# Sheet1.net
KiCad netlist of a schematic drawn in Altium Designer
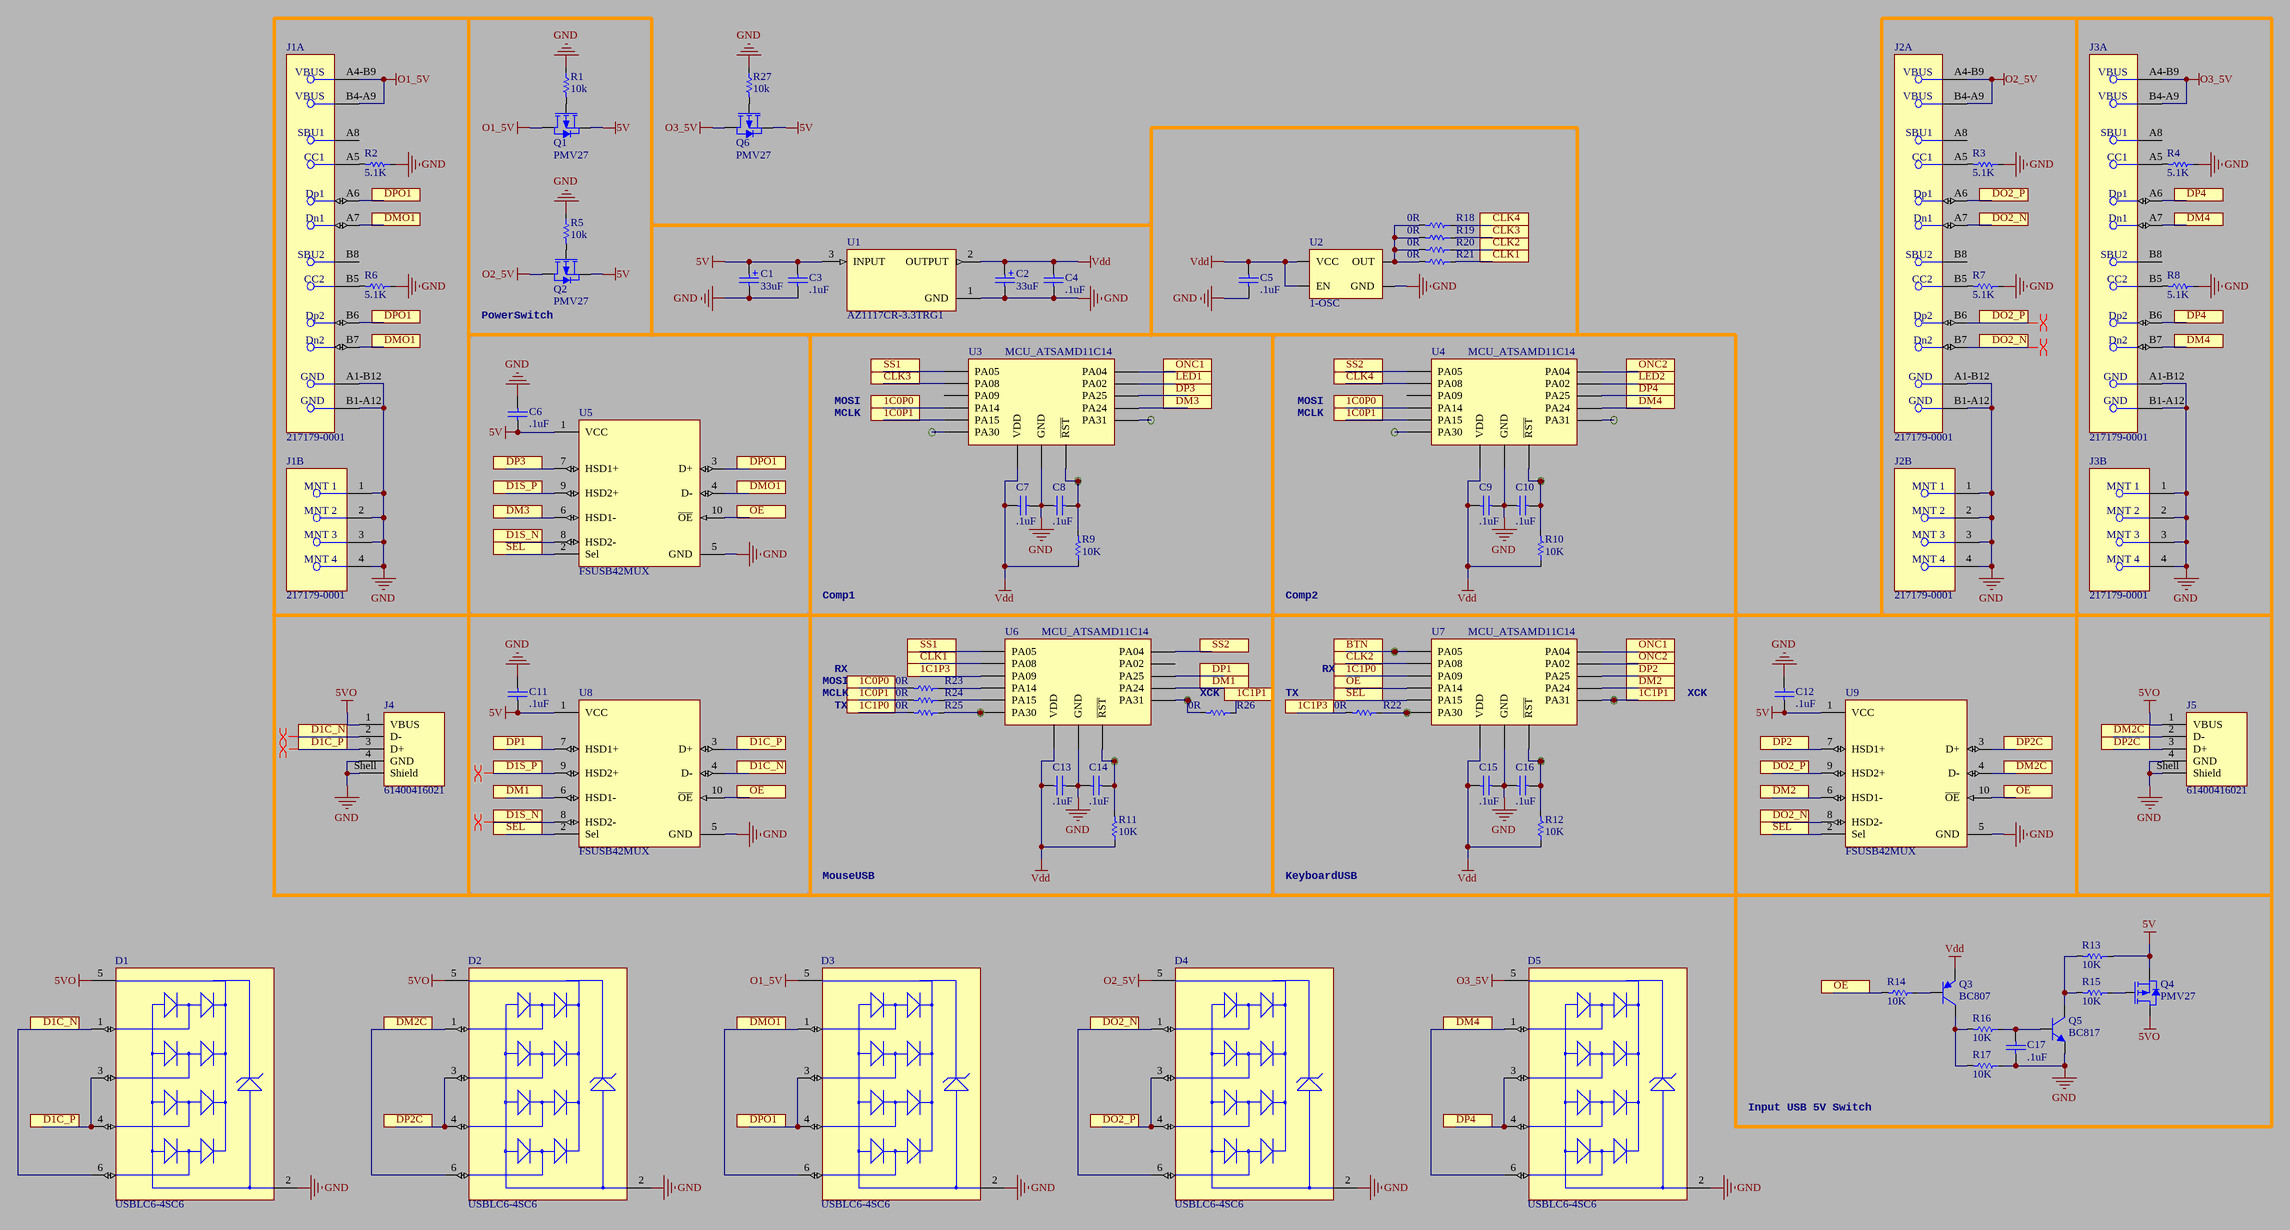
[diagram p0: Sheet1.SchDoc]

(export (version "E")
  (design (tool "Eeschema 10.0.6"))
  (components
    (comp (ref "C1")
      (value "33uF")
      (footprint "TH CAP AL-6.3X11MM-A1K2")
      (description "CAP, CER")
      (fields (field (name "Comment") "Cap Non-Pol"))
      (libsource (lib "A_Passive") (part "-Cap Pol"))
    )
    (comp (ref "C2")
      (value "33uF")
      (footprint "TH CAP AL-6.3X11MM-A1K2")
      (description "CAP, CER")
      (fields (field (name "Comment") "Cap Non-Pol"))
      (libsource (lib "A_Passive") (part "-Cap Pol"))
    )
    (comp (ref "C3")
      (value ".1uF")
      (footprint "Size_0603_N")
      (description "=Value")
      (fields (field (name "Comment") ".1uF, *, *, *, Size_0603_N"))
      (libsource (lib "A_Passive") (part "-Cap Non-Pol"))
    )
    (comp (ref "C4")
      (value ".1uF")
      (footprint "Size_0603_N")
      (description "=Value")
      (fields (field (name "Comment") ".1uF, *, *, *, Size_0603_N"))
      (libsource (lib "A_Passive") (part "-Cap Non-Pol"))
    )
    (comp (ref "C5")
      (value ".1uF")
      (footprint "Size_0603_N")
      (description "=Value")
      (fields (field (name "Comment") ".1uF, *, *, *, Size_0603_N"))
      (libsource (lib "A_Passive") (part "-Cap Non-Pol"))
    )
    (comp (ref "C6")
      (value ".1uF")
      (footprint "Size_0603_N")
      (description "=Value")
      (fields (field (name "Comment") ".1uF, *, *, *, Size_0603_N"))
      (libsource (lib "A_Passive") (part "-Cap Non-Pol"))
    )
    (comp (ref "C7")
      (value ".1uF")
      (footprint "Size_0603_N")
      (description "=Value")
      (fields (field (name "Comment") ".1uF, *, *, *, Size_0603_N"))
      (libsource (lib "A_Passive") (part "-Cap Non-Pol"))
    )
    (comp (ref "C8")
      (value ".1uF")
      (footprint "Size_0603_N")
      (description "=Value")
      (fields (field (name "Comment") ".1uF, *, *, *, Size_0603_N"))
      (libsource (lib "A_Passive") (part "-Cap Non-Pol"))
    )
    (comp (ref "C9")
      (value ".1uF")
      (footprint "Size_0603_N")
      (description "=Value")
      (fields (field (name "Comment") ".1uF, *, *, *, Size_0603_N"))
      (libsource (lib "A_Passive") (part "-Cap Non-Pol"))
    )
    (comp (ref "C10")
      (value ".1uF")
      (footprint "Size_0603_N")
      (description "=Value")
      (fields (field (name "Comment") ".1uF, *, *, *, Size_0603_N"))
      (libsource (lib "A_Passive") (part "-Cap Non-Pol"))
    )
    (comp (ref "C11")
      (value ".1uF")
      (footprint "Size_0603_N")
      (description "=Value")
      (fields (field (name "Comment") ".1uF, *, *, *, Size_0603_N"))
      (libsource (lib "A_Passive") (part "-Cap Non-Pol"))
    )
    (comp (ref "C12")
      (value ".1uF")
      (footprint "Size_0603_N")
      (description "=Value")
      (fields (field (name "Comment") ".1uF, *, *, *, Size_0603_N"))
      (libsource (lib "A_Passive") (part "-Cap Non-Pol"))
    )
    (comp (ref "C13")
      (value ".1uF")
      (footprint "Size_0603_N")
      (description "=Value")
      (fields (field (name "Comment") ".1uF, *, *, *, Size_0603_N"))
      (libsource (lib "A_Passive") (part "-Cap Non-Pol"))
    )
    (comp (ref "C14")
      (value ".1uF")
      (footprint "Size_0603_N")
      (description "=Value")
      (fields (field (name "Comment") ".1uF, *, *, *, Size_0603_N"))
      (libsource (lib "A_Passive") (part "-Cap Non-Pol"))
    )
    (comp (ref "C15")
      (value ".1uF")
      (footprint "Size_0603_N")
      (description "=Value")
      (fields (field (name "Comment") ".1uF, *, *, *, Size_0603_N"))
      (libsource (lib "A_Passive") (part "-Cap Non-Pol"))
    )
    (comp (ref "C16")
      (value ".1uF")
      (footprint "Size_0603_N")
      (description "=Value")
      (fields (field (name "Comment") ".1uF, *, *, *, Size_0603_N"))
      (libsource (lib "A_Passive") (part "-Cap Non-Pol"))
    )
    (comp (ref "C17")
      (value ".1uF")
      (footprint "Size_0603_N")
      (description "=Value")
      (fields (field (name "Comment") ".1uF, *, *, *, Size_0603_N"))
      (libsource (lib "A_Passive") (part "-Cap Non-Pol"))
    )
    (comp (ref "D1")
      (value "USBLC6-4SC6")
      (footprint "FP-SOT23-6L-MFG")
      (description "TVS DIODE 5.25V 17V SOT23-6")
      (fields
        (field (name "MANUFACTURER") "STMicroelectronics")
        (field (name "OCTOPART") "https://octopart.com/usblc6-4sc6-stmicroelectronics-347147")
      )
      (libsource (lib "Altium Content Vault") (part "3e70b616ccdc4c88b528e1820c4a7da"))
    )
    (comp (ref "D2")
      (value "USBLC6-4SC6")
      (footprint "FP-SOT23-6L-MFG")
      (description "TVS DIODE 5.25V 17V SOT23-6")
      (fields
        (field (name "MANUFACTURER") "STMicroelectronics")
        (field (name "OCTOPART") "https://octopart.com/usblc6-4sc6-stmicroelectronics-347147")
      )
      (libsource (lib "Altium Content Vault") (part "3e70b616ccdc4c88b528e1820c4a7da"))
    )
    (comp (ref "D3")
      (value "USBLC6-4SC6")
      (footprint "FP-SOT23-6L-MFG")
      (description "TVS DIODE 5.25V 17V SOT23-6")
      (fields
        (field (name "MANUFACTURER") "STMicroelectronics")
        (field (name "OCTOPART") "https://octopart.com/usblc6-4sc6-stmicroelectronics-347147")
      )
      (libsource (lib "Altium Content Vault") (part "3e70b616ccdc4c88b528e1820c4a7da"))
    )
    (comp (ref "D4")
      (value "USBLC6-4SC6")
      (footprint "FP-SOT23-6L-MFG")
      (description "TVS DIODE 5.25V 17V SOT23-6")
      (fields
        (field (name "MANUFACTURER") "STMicroelectronics")
        (field (name "OCTOPART") "https://octopart.com/usblc6-4sc6-stmicroelectronics-347147")
      )
      (libsource (lib "Altium Content Vault") (part "3e70b616ccdc4c88b528e1820c4a7da"))
    )
    (comp (ref "D5")
      (value "USBLC6-4SC6")
      (footprint "FP-SOT23-6L-MFG")
      (description "TVS DIODE 5.25V 17V SOT23-6")
      (fields
        (field (name "MANUFACTURER") "STMicroelectronics")
        (field (name "OCTOPART") "https://octopart.com/usblc6-4sc6-stmicroelectronics-347147")
      )
      (libsource (lib "Altium Content Vault") (part "3e70b616ccdc4c88b528e1820c4a7da"))
    )
    (comp (ref "J1")
      (value "217179-0001")
      (footprint "FP-2171790001-MFG")
      (description "CONN RCP USB2.0 TYP C 24P SMD RA")
      (libsource (lib "Altium Content Vault") (part "8b86497a633d14b3f74642136fc0ce6"))
    )
    (comp (ref "J2")
      (value "217179-0001")
      (footprint "FP-2171790001-MFG")
      (description "CONN RCP USB2.0 TYP C 24P SMD RA")
      (libsource (lib "Altium Content Vault") (part "8b86497a633d14b3f74642136fc0ce6"))
    )
    (comp (ref "J3")
      (value "217179-0001")
      (footprint "FP-2171790001-MFG")
      (description "CONN RCP USB2.0 TYP C 24P SMD RA")
      (libsource (lib "Altium Content Vault") (part "8b86497a633d14b3f74642136fc0ce6"))
    )
    (comp (ref "J4")
      (value "61400416021")
      (footprint "61400416021")
      (libsource (lib "Altium Content Vault") (part "USB 2.0_Type A_Receptacle_1 Port"))
    )
    (comp (ref "J5")
      (value "61400416021")
      (footprint "61400416021")
      (libsource (lib "Altium Content Vault") (part "USB 2.0_Type A_Receptacle_1 Port"))
    )
    (comp (ref "JP1")
      (value "Pogo_Contact")
      (footprint "Pogo_254")
      (libsource (lib "A_Connector") (part "Pogo_Contact"))
    )
    (comp (ref "JP2")
      (value "Pogo_Contact")
      (footprint "Pogo_254")
      (libsource (lib "A_Connector") (part "Pogo_Contact"))
    )
    (comp (ref "JP3")
      (value "Pogo_Contact")
      (footprint "Pogo_254")
      (libsource (lib "A_Connector") (part "Pogo_Contact"))
    )
    (comp (ref "JP4")
      (value "Pogo_Contact")
      (footprint "Pogo_254")
      (libsource (lib "A_Connector") (part "Pogo_Contact"))
    )
    (comp (ref "JP5")
      (value "Pogo_Contact")
      (footprint "Pogo_254")
      (libsource (lib "A_Connector") (part "Pogo_Contact"))
    )
    (comp (ref "JP6")
      (value "Pogo_Contact")
      (footprint "Pogo_254")
      (libsource (lib "A_Connector") (part "Pogo_Contact"))
    )
    (comp (ref "JP7")
      (value "Pogo_Contact")
      (footprint "Pogo_254")
      (libsource (lib "A_Connector") (part "Pogo_Contact"))
    )
    (comp (ref "JP8")
      (value "Pogo_Contact")
      (footprint "Pogo_254")
      (libsource (lib "A_Connector") (part "Pogo_Contact"))
    )
    (comp (ref "JP9")
      (value "Pogo_Contact")
      (footprint "Pogo_254")
      (libsource (lib "A_Connector") (part "Pogo_Contact"))
    )
    (comp (ref "JP10")
      (value "Pogo_Contact")
      (footprint "Pogo_254")
      (libsource (lib "A_Connector") (part "Pogo_Contact"))
    )
    (comp (ref "JP11")
      (value "Pogo_Contact")
      (footprint "Pogo_254")
      (libsource (lib "A_Connector") (part "Pogo_Contact"))
    )
    (comp (ref "JP12")
      (value "Pogo_Contact")
      (footprint "Pogo_254")
      (libsource (lib "A_Connector") (part "Pogo_Contact"))
    )
    (comp (ref "JP13")
      (value "Pogo_Contact")
      (footprint "Pogo_254")
      (libsource (lib "A_Connector") (part "Pogo_Contact"))
    )
    (comp (ref "Q1")
      (value "PMV27")
      (footprint "SOT23-3")
      (description "P-Channel Enhancement Mosfet")
      (libsource (lib "A_Semi") (part "1-Mosfet_P"))
    )
    (comp (ref "Q2")
      (value "PMV27")
      (footprint "SOT23-3")
      (description "P-Channel Enhancement Mosfet")
      (libsource (lib "A_Semi") (part "1-Mosfet_P"))
    )
    (comp (ref "Q3") (value "BC807") (footprint "SOT23-3") (libsource (lib "A_Semi") (part "1-BJT-PNP")))
    (comp (ref "Q4")
      (value "PMV27")
      (footprint "SOT23-3")
      (description "P-Channel Enhancement Mosfet")
      (libsource (lib "A_Semi") (part "1-Mosfet_P"))
    )
    (comp (ref "Q5")
      (value "BC817")
      (footprint "SOT23-3")
      (description "NPN General Purpose")
      (libsource (lib "A_Semi") (part "1-BJT_NPN"))
    )
    (comp (ref "Q6")
      (value "PMV27")
      (footprint "SOT23-3")
      (description "P-Channel Enhancement Mosfet")
      (libsource (lib "A_Semi") (part "1-Mosfet_P"))
    )
    (comp (ref "R1")
      (value "10k")
      (footprint "Size_0603_N")
      (description "=Value")
      (fields (field (name "TOLERANCE") "1%") (field (name "Comment") "10k, *"))
      (libsource (lib "A_Passive") (part "-Res"))
    )
    (comp (ref "R2")
      (value "5.1K")
      (footprint "Size_0603_N")
      (description "=Value")
      (fields (field (name "TOLERANCE") "1%") (field (name "Comment") "5.1K, *"))
      (libsource (lib "A_Passive") (part "-Res"))
    )
    (comp (ref "R3")
      (value "5.1K")
      (footprint "Size_0603_N")
      (description "=Value")
      (fields (field (name "TOLERANCE") "1%") (field (name "Comment") "5.1K, *"))
      (libsource (lib "A_Passive") (part "-Res"))
    )
    (comp (ref "R4")
      (value "5.1K")
      (footprint "Size_0603_N")
      (description "=Value")
      (fields (field (name "TOLERANCE") "1%") (field (name "Comment") "5.1K, *"))
      (libsource (lib "A_Passive") (part "-Res"))
    )
    (comp (ref "R5")
      (value "10k")
      (footprint "Size_0603_N")
      (description "=Value")
      (fields (field (name "TOLERANCE") "1%") (field (name "Comment") "10k, *"))
      (libsource (lib "A_Passive") (part "-Res"))
    )
    (comp (ref "R6")
      (value "5.1K")
      (footprint "Size_0603_N")
      (description "=Value")
      (fields (field (name "TOLERANCE") "1%") (field (name "Comment") "5.1K, *"))
      (libsource (lib "A_Passive") (part "-Res"))
    )
    (comp (ref "R7")
      (value "5.1K")
      (footprint "Size_0603_N")
      (description "=Value")
      (fields (field (name "TOLERANCE") "1%") (field (name "Comment") "5.1K, *"))
      (libsource (lib "A_Passive") (part "-Res"))
    )
    (comp (ref "R8")
      (value "5.1K")
      (footprint "Size_0603_N")
      (description "=Value")
      (fields (field (name "TOLERANCE") "1%") (field (name "Comment") "5.1K, *"))
      (libsource (lib "A_Passive") (part "-Res"))
    )
    (comp (ref "R9")
      (value "10K")
      (footprint "Size_0603_N")
      (description "=Value")
      (fields (field (name "TOLERANCE") "1%") (field (name "Comment") "10K, *"))
      (libsource (lib "A_Passive") (part "-Res"))
    )
    (comp (ref "R10")
      (value "10K")
      (footprint "Size_0603_N")
      (description "=Value")
      (fields (field (name "TOLERANCE") "1%") (field (name "Comment") "10K, *"))
      (libsource (lib "A_Passive") (part "-Res"))
    )
    (comp (ref "R11")
      (value "10K")
      (footprint "Size_0603_N")
      (description "=Value")
      (fields (field (name "TOLERANCE") "1%") (field (name "Comment") "10K, *"))
      (libsource (lib "A_Passive") (part "-Res"))
    )
    (comp (ref "R12")
      (value "10K")
      (footprint "Size_0603_N")
      (description "=Value")
      (fields (field (name "TOLERANCE") "1%") (field (name "Comment") "10K, *"))
      (libsource (lib "A_Passive") (part "-Res"))
    )
    (comp (ref "R13")
      (value "10K")
      (footprint "Size_0603_N")
      (description "=Value")
      (fields (field (name "TOLERANCE") "1%") (field (name "Comment") "10K, *"))
      (libsource (lib "A_Passive") (part "-Res"))
    )
    (comp (ref "R14")
      (value "10K")
      (footprint "Size_0603_N")
      (description "=Value")
      (fields (field (name "TOLERANCE") "1%") (field (name "Comment") "10K, *"))
      (libsource (lib "A_Passive") (part "-Res"))
    )
    (comp (ref "R15")
      (value "10K")
      (footprint "Size_0603_N")
      (description "=Value")
      (fields (field (name "TOLERANCE") "1%") (field (name "Comment") "10K, *"))
      (libsource (lib "A_Passive") (part "-Res"))
    )
    (comp (ref "R16")
      (value "10K")
      (footprint "Size_0603_N")
      (description "=Value")
      (fields (field (name "TOLERANCE") "1%") (field (name "Comment") "10K, *"))
      (libsource (lib "A_Passive") (part "-Res"))
    )
    (comp (ref "R17")
      (value "10K")
      (footprint "Size_0603_N")
      (description "=Value")
      (fields (field (name "TOLERANCE") "1%") (field (name "Comment") "10K, *"))
      (libsource (lib "A_Passive") (part "-Res"))
    )
    (comp (ref "R18")
      (value "0R")
      (footprint "Size_0603_N")
      (description "=Value")
      (fields (field (name "TOLERANCE") "1%") (field (name "Comment") "0R, *"))
      (libsource (lib "A_Passive") (part "-Res"))
    )
    (comp (ref "R19")
      (value "0R")
      (footprint "Size_0603_N")
      (description "=Value")
      (fields (field (name "TOLERANCE") "1%") (field (name "Comment") "0R, *"))
      (libsource (lib "A_Passive") (part "-Res"))
    )
    (comp (ref "R20")
      (value "0R")
      (footprint "Size_0603_N")
      (description "=Value")
      (fields (field (name "TOLERANCE") "1%") (field (name "Comment") "0R, *"))
      (libsource (lib "A_Passive") (part "-Res"))
    )
    (comp (ref "R21")
      (value "0R")
      (footprint "Size_0603_N")
      (description "=Value")
      (fields (field (name "TOLERANCE") "1%") (field (name "Comment") "0R, *"))
      (libsource (lib "A_Passive") (part "-Res"))
    )
    (comp (ref "R22")
      (value "0R")
      (footprint "Size_0603_N")
      (description "=Value")
      (fields (field (name "TOLERANCE") "1%") (field (name "Comment") "0R, *"))
      (libsource (lib "A_Passive") (part "-Res"))
    )
    (comp (ref "R23")
      (value "0R")
      (footprint "Size_0603_N")
      (description "=Value")
      (fields (field (name "TOLERANCE") "1%") (field (name "Comment") "0R, *"))
      (libsource (lib "A_Passive") (part "-Res"))
    )
    (comp (ref "R24")
      (value "0R")
      (footprint "Size_0603_N")
      (description "=Value")
      (fields (field (name "TOLERANCE") "1%") (field (name "Comment") "0R, *"))
      (libsource (lib "A_Passive") (part "-Res"))
    )
    (comp (ref "R25")
      (value "0R")
      (footprint "Size_0603_N")
      (description "=Value")
      (fields (field (name "TOLERANCE") "1%") (field (name "Comment") "0R, *"))
      (libsource (lib "A_Passive") (part "-Res"))
    )
    (comp (ref "R26")
      (value "0R")
      (footprint "Size_0603_N")
      (description "=Value")
      (fields (field (name "TOLERANCE") "1%") (field (name "Comment") "0R, *"))
      (libsource (lib "A_Passive") (part "-Res"))
    )
    (comp (ref "R27")
      (value "10k")
      (footprint "Size_0603_N")
      (description "=Value")
      (fields (field (name "TOLERANCE") "1%") (field (name "Comment") "10k, *"))
      (libsource (lib "A_Passive") (part "-Res"))
    )
    (comp (ref "U1")
      (value "AZ1117CR-3.3TRG1")
      (footprint "FP-SOT89-MFG")
      (description "IC REG LINEAR 3.3V 800MA SOT89")
      (fields
        (field (name "OCTOPART") "https://octopart.com/az1117cr-3.3trg1-diodes+inc.-30954805")
        (field (name "MANUFACTURER") "Diodes Inc.")
      )
      (libsource (lib "Altium Content Vault") (part "80dc4d5e0c5bf011f486f511683fde3"))
    )
    (comp (ref "U2") (value "1-OSC") (footprint "2520osc") (libsource (lib "A_Semi") (part "1-OSC")))
    (comp (ref "U3")
      (value "MCU_ATSAMD11C14")
      (footprint "SOIC127P600X175-14N")
      (libsource (lib "A_Semi") (part "MCU_ATSAMD11C14"))
    )
    (comp (ref "U4")
      (value "MCU_ATSAMD11C14")
      (footprint "SOIC127P600X175-14N")
      (libsource (lib "A_Semi") (part "MCU_ATSAMD11C14"))
    )
    (comp (ref "U5")
      (value "FSUSB42MUX")
      (footprint "FP-846AP-MFG")
      (description "IC USB SWITCH DPDT 10MSOP")
      (fields (field (name "VOLTAGE") "4.3V"))
      (libsource (lib "Altium Content Vault") (part "e0bd5e1b4e0e4edc77f3356c64bf8f9"))
    )
    (comp (ref "U6")
      (value "MCU_ATSAMD11C14")
      (footprint "SOIC127P600X175-14N")
      (libsource (lib "A_Semi") (part "MCU_ATSAMD11C14"))
    )
    (comp (ref "U7")
      (value "MCU_ATSAMD11C14")
      (footprint "SOIC127P600X175-14N")
      (libsource (lib "A_Semi") (part "MCU_ATSAMD11C14"))
    )
    (comp (ref "U8")
      (value "FSUSB42MUX")
      (footprint "FP-846AP-MFG")
      (description "IC USB SWITCH DPDT 10MSOP")
      (fields (field (name "VOLTAGE") "4.3V"))
      (libsource (lib "Altium Content Vault") (part "e0bd5e1b4e0e4edc77f3356c64bf8f9"))
    )
    (comp (ref "U9")
      (value "FSUSB42MUX")
      (footprint "FP-846AP-MFG")
      (description "IC USB SWITCH DPDT 10MSOP")
      (fields (field (name "VOLTAGE") "4.3V"))
      (libsource (lib "Altium Content Vault") (part "e0bd5e1b4e0e4edc77f3356c64bf8f9"))
    )
  )
  (nets
    (net (code "1") (name "/1C0P0") (class "Default")
      (node (ref "R23") (pin "2") (pinfunction "2_2") (pintype "passive"))
      (node (ref "U3") (pin "4") (pinfunction "PA14_4") (pintype "passive"))
      (node (ref "U4") (pin "4") (pinfunction "PA14_4") (pintype "passive"))
    )
    (net (code "2") (name "/1C0P1") (class "Default")
      (node (ref "R24") (pin "2") (pinfunction "2_2") (pintype "passive"))
      (node (ref "U3") (pin "5") (pinfunction "PA15_5") (pintype "passive"))
      (node (ref "U4") (pin "5") (pinfunction "PA15_5") (pintype "passive"))
    )
    (net (code "3") (name "/1C1P0") (class "Default")
      (node (ref "R25") (pin "2") (pinfunction "2_2") (pintype "passive"))
      (node (ref "U7") (pin "3") (pinfunction "PA09_3") (pintype "passive"))
    )
    (net (code "4") (name "/1C1P1") (class "Default")
      (node (ref "JP9") (pin "1") (pinfunction "1_1") (pintype "passive"))
      (node (ref "R26") (pin "1") (pinfunction "1_1") (pintype "passive"))
      (node (ref "U7") (pin "8") (pinfunction "PA31_8") (pintype "passive"))
    )
    (net (code "5") (name "/1C1P3") (class "Default")
      (node (ref "R22") (pin "2") (pinfunction "2_2") (pintype "passive"))
      (node (ref "U6") (pin "3") (pinfunction "PA09_3") (pintype "passive"))
    )
    (net (code "6") (name "/BTN") (class "Default")
      (node (ref "JP7") (pin "1") (pinfunction "1_1") (pintype "passive"))
      (node (ref "U7") (pin "1") (pinfunction "PA05_1") (pintype "passive"))
    )
    (net (code "7") (name "/CLK1") (class "Default")
      (node (ref "R21") (pin "1") (pinfunction "1_1") (pintype "passive"))
      (node (ref "U6") (pin "2") (pinfunction "PA08_2") (pintype "passive"))
    )
    (net (code "8") (name "/CLK2") (class "Default")
      (node (ref "R20") (pin "1") (pinfunction "1_1") (pintype "passive"))
      (node (ref "U7") (pin "2") (pinfunction "PA08_2") (pintype "passive"))
    )
    (net (code "9") (name "/CLK3") (class "Default")
      (node (ref "R19") (pin "1") (pinfunction "1_1") (pintype "passive"))
      (node (ref "U3") (pin "2") (pinfunction "PA08_2") (pintype "passive"))
    )
    (net (code "10") (name "/CLK4") (class "Default")
      (node (ref "R18") (pin "1") (pinfunction "1_1") (pintype "passive"))
      (node (ref "U4") (pin "2") (pinfunction "PA08_2") (pintype "passive"))
    )
    (net (code "11") (name "/D1C_N") (class "Default")
      (node (ref "D1") (pin "1") (pinfunction "I/O1_1") (pintype "bidirectional"))
      (node (ref "D1") (pin "6") (pinfunction "I/O4_6") (pintype "bidirectional"))
      (node (ref "J4") (pin "2") (pinfunction "D-_2") (pintype "passive"))
      (node (ref "U8") (pin "4") (pinfunction "D-_4") (pintype "bidirectional"))
    )
    (net (code "12") (name "/D1C_P") (class "Default")
      (node (ref "D1") (pin "3") (pinfunction "I/O2_3") (pintype "bidirectional"))
      (node (ref "D1") (pin "4") (pinfunction "I/O3_4") (pintype "bidirectional"))
      (node (ref "J4") (pin "3") (pinfunction "D+_3") (pintype "passive"))
      (node (ref "U8") (pin "3") (pinfunction "D+_3") (pintype "bidirectional"))
    )
    (net (code "13") (name "/D1S_N") (class "Default")
      (node (ref "U5") (pin "8") (pinfunction "HSD2-_8") (pintype "bidirectional"))
      (node (ref "U8") (pin "8") (pinfunction "HSD2-_8") (pintype "bidirectional"))
    )
    (net (code "14") (name "/D1S_P") (class "Default")
      (node (ref "U5") (pin "9") (pinfunction "HSD2+_9") (pintype "bidirectional"))
      (node (ref "U8") (pin "9") (pinfunction "HSD2+_9") (pintype "bidirectional"))
    )
    (net (code "15") (name "/DM1") (class "Default")
      (node (ref "U6") (pin "9") (pinfunction "PA24_9") (pintype "passive"))
      (node (ref "U8") (pin "6") (pinfunction "HSD1-_6") (pintype "bidirectional"))
    )
    (net (code "16") (name "/DM2") (class "Default")
      (node (ref "U7") (pin "9") (pinfunction "PA24_9") (pintype "passive"))
      (node (ref "U9") (pin "6") (pinfunction "HSD1-_6") (pintype "bidirectional"))
    )
    (net (code "17") (name "/DM2C") (class "Default")
      (node (ref "D2") (pin "1") (pinfunction "I/O1_1") (pintype "bidirectional"))
      (node (ref "D2") (pin "6") (pinfunction "I/O4_6") (pintype "bidirectional"))
      (node (ref "J5") (pin "2") (pinfunction "D-_2") (pintype "passive"))
      (node (ref "U9") (pin "4") (pinfunction "D-_4") (pintype "bidirectional"))
    )
    (net (code "18") (name "/DM3") (class "Default")
      (node (ref "U3") (pin "9") (pinfunction "PA24_9") (pintype "passive"))
      (node (ref "U5") (pin "6") (pinfunction "HSD1-_6") (pintype "bidirectional"))
    )
    (net (code "19") (name "/DM4") (class "Default")
      (node (ref "D5") (pin "1") (pinfunction "I/O1_1") (pintype "bidirectional"))
      (node (ref "D5") (pin "6") (pinfunction "I/O4_6") (pintype "bidirectional"))
      (node (ref "J3") (pin "A7") (pinfunction "Dn1_A7") (pintype "bidirectional"))
      (node (ref "J3") (pin "B7") (pinfunction "Dn2_B7") (pintype "bidirectional"))
      (node (ref "U4") (pin "9") (pinfunction "PA24_9") (pintype "passive"))
    )
    (net (code "20") (name "/DMO1") (class "Default")
      (node (ref "D3") (pin "1") (pinfunction "I/O1_1") (pintype "bidirectional"))
      (node (ref "D3") (pin "6") (pinfunction "I/O4_6") (pintype "bidirectional"))
      (node (ref "J1") (pin "A7") (pinfunction "Dn1_A7") (pintype "bidirectional"))
      (node (ref "J1") (pin "B7") (pinfunction "Dn2_B7") (pintype "bidirectional"))
      (node (ref "U5") (pin "4") (pinfunction "D-_4") (pintype "bidirectional"))
    )
    (net (code "21") (name "/DO2_N") (class "Default")
      (node (ref "D4") (pin "1") (pinfunction "I/O1_1") (pintype "bidirectional"))
      (node (ref "D4") (pin "6") (pinfunction "I/O4_6") (pintype "bidirectional"))
      (node (ref "J2") (pin "A7") (pinfunction "Dn1_A7") (pintype "bidirectional"))
      (node (ref "J2") (pin "B7") (pinfunction "Dn2_B7") (pintype "bidirectional"))
      (node (ref "U9") (pin "8") (pinfunction "HSD2-_8") (pintype "bidirectional"))
    )
    (net (code "22") (name "/DO2_P") (class "Default")
      (node (ref "D4") (pin "3") (pinfunction "I/O2_3") (pintype "bidirectional"))
      (node (ref "D4") (pin "4") (pinfunction "I/O3_4") (pintype "bidirectional"))
      (node (ref "J2") (pin "A6") (pinfunction "Dp1_A6") (pintype "bidirectional"))
      (node (ref "J2") (pin "B6") (pinfunction "Dp2_B6") (pintype "bidirectional"))
      (node (ref "U9") (pin "9") (pinfunction "HSD2+_9") (pintype "bidirectional"))
    )
    (net (code "23") (name "/DP1") (class "Default")
      (node (ref "U6") (pin "10") (pinfunction "PA25_10") (pintype "passive"))
      (node (ref "U8") (pin "7") (pinfunction "HSD1+_7") (pintype "bidirectional"))
    )
    (net (code "24") (name "/DP2") (class "Default")
      (node (ref "U7") (pin "10") (pinfunction "PA25_10") (pintype "passive"))
      (node (ref "U9") (pin "7") (pinfunction "HSD1+_7") (pintype "bidirectional"))
    )
    (net (code "25") (name "/DP2C") (class "Default")
      (node (ref "D2") (pin "3") (pinfunction "I/O2_3") (pintype "bidirectional"))
      (node (ref "D2") (pin "4") (pinfunction "I/O3_4") (pintype "bidirectional"))
      (node (ref "J5") (pin "3") (pinfunction "D+_3") (pintype "passive"))
      (node (ref "U9") (pin "3") (pinfunction "D+_3") (pintype "bidirectional"))
    )
    (net (code "26") (name "/DP3") (class "Default")
      (node (ref "U3") (pin "10") (pinfunction "PA25_10") (pintype "passive"))
      (node (ref "U5") (pin "7") (pinfunction "HSD1+_7") (pintype "bidirectional"))
    )
    (net (code "27") (name "/DP4") (class "Default")
      (node (ref "D5") (pin "3") (pinfunction "I/O2_3") (pintype "bidirectional"))
      (node (ref "D5") (pin "4") (pinfunction "I/O3_4") (pintype "bidirectional"))
      (node (ref "J3") (pin "A6") (pinfunction "Dp1_A6") (pintype "bidirectional"))
      (node (ref "J3") (pin "B6") (pinfunction "Dp2_B6") (pintype "bidirectional"))
      (node (ref "U4") (pin "10") (pinfunction "PA25_10") (pintype "passive"))
    )
    (net (code "28") (name "/DPO1") (class "Default")
      (node (ref "D3") (pin "3") (pinfunction "I/O2_3") (pintype "bidirectional"))
      (node (ref "D3") (pin "4") (pinfunction "I/O3_4") (pintype "bidirectional"))
      (node (ref "J1") (pin "A6") (pinfunction "Dp1_A6") (pintype "bidirectional"))
      (node (ref "J1") (pin "B6") (pinfunction "Dp2_B6") (pintype "bidirectional"))
      (node (ref "U5") (pin "3") (pinfunction "D+_3") (pintype "bidirectional"))
    )
    (net (code "29") (name "/LED1") (class "Default")
      (node (ref "U3") (pin "13") (pinfunction "PA02_13") (pintype "passive"))
    )
    (net (code "30") (name "/LED2") (class "Default")
      (node (ref "U4") (pin "13") (pinfunction "PA02_13") (pintype "passive"))
    )
    (net (code "31") (name "/OE") (class "Default")
      (node (ref "R14") (pin "2") (pinfunction "2_2") (pintype "passive"))
      (node (ref "U5") (pin "10") (pinfunction "~{OE}_10") (pintype "input"))
      (node (ref "U7") (pin "4") (pinfunction "PA14_4") (pintype "passive"))
      (node (ref "U8") (pin "10") (pinfunction "~{OE}_10") (pintype "input"))
      (node (ref "U9") (pin "10") (pinfunction "~{OE}_10") (pintype "input"))
    )
    (net (code "32") (name "/ONC1") (class "Default")
      (node (ref "U3") (pin "14") (pinfunction "PA04_14") (pintype "passive"))
      (node (ref "U7") (pin "14") (pinfunction "PA04_14") (pintype "passive"))
    )
    (net (code "33") (name "/ONC2") (class "Default")
      (node (ref "U4") (pin "14") (pinfunction "PA04_14") (pintype "passive"))
      (node (ref "U7") (pin "13") (pinfunction "PA02_13") (pintype "passive"))
    )
    (net (code "34") (name "/SEL") (class "Default")
      (node (ref "U5") (pin "2") (pinfunction "Sel_2") (pintype "passive"))
      (node (ref "U7") (pin "5") (pinfunction "PA15_5") (pintype "passive"))
      (node (ref "U8") (pin "2") (pinfunction "Sel_2") (pintype "passive"))
      (node (ref "U9") (pin "2") (pinfunction "Sel_2") (pintype "passive"))
    )
    (net (code "35") (name "/SS1") (class "Default")
      (node (ref "U3") (pin "1") (pinfunction "PA05_1") (pintype "passive"))
      (node (ref "U6") (pin "1") (pinfunction "PA05_1") (pintype "passive"))
    )
    (net (code "36") (name "/SS2") (class "Default")
      (node (ref "U4") (pin "1") (pinfunction "PA05_1") (pintype "passive"))
      (node (ref "U6") (pin "14") (pinfunction "PA04_14") (pintype "passive"))
    )
    (net (code "37") (name "5V") (class "Default")
      (node (ref "C1") (pin "1") (pinfunction "1_1") (pintype "passive"))
      (node (ref "C11") (pin "1") (pinfunction "1_1") (pintype "passive"))
      (node (ref "C12") (pin "1") (pinfunction "1_1") (pintype "passive"))
      (node (ref "C3") (pin "2") (pinfunction "2_2") (pintype "passive"))
      (node (ref "C6") (pin "1") (pinfunction "1_1") (pintype "passive"))
      (node (ref "Q1") (pin "3") (pinfunction "S_3") (pintype "passive"))
      (node (ref "Q2") (pin "3") (pinfunction "S_3") (pintype "passive"))
      (node (ref "Q4") (pin "3") (pinfunction "S_3") (pintype "passive"))
      (node (ref "Q6") (pin "3") (pinfunction "S_3") (pintype "passive"))
      (node (ref "R13") (pin "1") (pinfunction "1_1") (pintype "passive"))
      (node (ref "U1") (pin "3") (pinfunction "INPUT_3") (pintype "input"))
      (node (ref "U5") (pin "1") (pinfunction "VCC_1") (pintype "power_in"))
      (node (ref "U8") (pin "1") (pinfunction "VCC_1") (pintype "power_in"))
      (node (ref "U9") (pin "1") (pinfunction "VCC_1") (pintype "power_in"))
    )
    (net (code "38") (name "5VO") (class "Default")
      (node (ref "D1") (pin "5") (pinfunction "VBUS_5") (pintype "power_in"))
      (node (ref "D2") (pin "5") (pinfunction "VBUS_5") (pintype "power_in"))
      (node (ref "J4") (pin "1") (pinfunction "VBUS_1") (pintype "passive"))
      (node (ref "J5") (pin "1") (pinfunction "VBUS_1") (pintype "passive"))
      (node (ref "Q4") (pin "2") (pinfunction "D_2") (pintype "passive"))
    )
    (net (code "39") (name "GND") (class "Default")
      (node (ref "C1") (pin "2") (pinfunction "2_2") (pintype "passive"))
      (node (ref "C10") (pin "1") (pinfunction "1_1") (pintype "passive"))
      (node (ref "C11") (pin "2") (pinfunction "2_2") (pintype "passive"))
      (node (ref "C12") (pin "2") (pinfunction "2_2") (pintype "passive"))
      (node (ref "C13") (pin "2") (pinfunction "2_2") (pintype "passive"))
      (node (ref "C14") (pin "1") (pinfunction "1_1") (pintype "passive"))
      (node (ref "C15") (pin "2") (pinfunction "2_2") (pintype "passive"))
      (node (ref "C16") (pin "1") (pinfunction "1_1") (pintype "passive"))
      (node (ref "C17") (pin "1") (pinfunction "1_1") (pintype "passive"))
      (node (ref "C2") (pin "2") (pinfunction "2_2") (pintype "passive"))
      (node (ref "C3") (pin "1") (pinfunction "1_1") (pintype "passive"))
      (node (ref "C4") (pin "1") (pinfunction "1_1") (pintype "passive"))
      (node (ref "C5") (pin "1") (pinfunction "1_1") (pintype "passive"))
      (node (ref "C6") (pin "2") (pinfunction "2_2") (pintype "passive"))
      (node (ref "C7") (pin "2") (pinfunction "2_2") (pintype "passive"))
      (node (ref "C8") (pin "1") (pinfunction "1_1") (pintype "passive"))
      (node (ref "C9") (pin "2") (pinfunction "2_2") (pintype "passive"))
      (node (ref "D1") (pin "2") (pinfunction "GND_2") (pintype "power_in"))
      (node (ref "D2") (pin "2") (pinfunction "GND_2") (pintype "power_in"))
      (node (ref "D3") (pin "2") (pinfunction "GND_2") (pintype "power_in"))
      (node (ref "D4") (pin "2") (pinfunction "GND_2") (pintype "power_in"))
      (node (ref "D5") (pin "2") (pinfunction "GND_2") (pintype "power_in"))
      (node (ref "J1") (pin "1") (pinfunction "MNT_1_1") (pintype "passive"))
      (node (ref "J1") (pin "2") (pinfunction "MNT_2_2") (pintype "passive"))
      (node (ref "J1") (pin "3") (pinfunction "MNT_3_3") (pintype "power_in"))
      (node (ref "J1") (pin "4") (pinfunction "MNT_4_4") (pintype "power_in"))
      (node (ref "J1") (pin "A1-B12") (pinfunction "GND_A1-B12") (pintype "power_in"))
      (node (ref "J1") (pin "B1-A12") (pinfunction "GND_B1-A12") (pintype "power_in"))
      (node (ref "J2") (pin "1") (pinfunction "MNT_1_1") (pintype "passive"))
      (node (ref "J2") (pin "2") (pinfunction "MNT_2_2") (pintype "passive"))
      (node (ref "J2") (pin "3") (pinfunction "MNT_3_3") (pintype "power_in"))
      (node (ref "J2") (pin "4") (pinfunction "MNT_4_4") (pintype "power_in"))
      (node (ref "J2") (pin "A1-B12") (pinfunction "GND_A1-B12") (pintype "power_in"))
      (node (ref "J2") (pin "B1-A12") (pinfunction "GND_B1-A12") (pintype "power_in"))
      (node (ref "J3") (pin "1") (pinfunction "MNT_1_1") (pintype "passive"))
      (node (ref "J3") (pin "2") (pinfunction "MNT_2_2") (pintype "passive"))
      (node (ref "J3") (pin "3") (pinfunction "MNT_3_3") (pintype "power_in"))
      (node (ref "J3") (pin "4") (pinfunction "MNT_4_4") (pintype "power_in"))
      (node (ref "J3") (pin "A1-B12") (pinfunction "GND_A1-B12") (pintype "power_in"))
      (node (ref "J3") (pin "B1-A12") (pinfunction "GND_B1-A12") (pintype "power_in"))
      (node (ref "J4") (pin "4") (pinfunction "GND_4") (pintype "passive"))
      (node (ref "J4") (pin "Shell") (pinfunction "Shield_Shell") (pintype "passive"))
      (node (ref "J5") (pin "4") (pinfunction "GND_4") (pintype "passive"))
      (node (ref "J5") (pin "Shell") (pinfunction "Shield_Shell") (pintype "passive"))
      (node (ref "Q5") (pin "2") (pinfunction "E_2") (pintype "passive"))
      (node (ref "R1") (pin "1") (pinfunction "1_1") (pintype "passive"))
      (node (ref "R17") (pin "1") (pinfunction "1_1") (pintype "passive"))
      (node (ref "R2") (pin "1") (pinfunction "1_1") (pintype "passive"))
      (node (ref "R27") (pin "1") (pinfunction "1_1") (pintype "passive"))
      (node (ref "R3") (pin "1") (pinfunction "1_1") (pintype "passive"))
      (node (ref "R4") (pin "1") (pinfunction "1_1") (pintype "passive"))
      (node (ref "R5") (pin "1") (pinfunction "1_1") (pintype "passive"))
      (node (ref "R6") (pin "1") (pinfunction "1_1") (pintype "passive"))
      (node (ref "R7") (pin "1") (pinfunction "1_1") (pintype "passive"))
      (node (ref "R8") (pin "1") (pinfunction "1_1") (pintype "passive"))
      (node (ref "U1") (pin "1") (pinfunction "GND_1") (pintype "power_in"))
      (node (ref "U2") (pin "2") (pinfunction "GND_2") (pintype "passive"))
      (node (ref "U3") (pin "11") (pinfunction "GND_11") (pintype "passive"))
      (node (ref "U4") (pin "11") (pinfunction "GND_11") (pintype "passive"))
      (node (ref "U5") (pin "5") (pinfunction "GND_5") (pintype "power_in"))
      (node (ref "U6") (pin "11") (pinfunction "GND_11") (pintype "passive"))
      (node (ref "U7") (pin "11") (pinfunction "GND_11") (pintype "passive"))
      (node (ref "U8") (pin "5") (pinfunction "GND_5") (pintype "power_in"))
      (node (ref "U9") (pin "5") (pinfunction "GND_5") (pintype "power_in"))
    )
    (net (code "40") (name "Net-(J1A-CC1)") (class "Default")
      (node (ref "J1") (pin "A5") (pinfunction "CC1_A5") (pintype "passive"))
      (node (ref "R2") (pin "2") (pinfunction "2_2") (pintype "passive"))
    )
    (net (code "41") (name "Net-(J1A-CC2)") (class "Default")
      (node (ref "J1") (pin "B5") (pinfunction "CC2_B5") (pintype "passive"))
      (node (ref "R6") (pin "2") (pinfunction "2_2") (pintype "passive"))
    )
    (net (code "42") (name "Net-(J2A-CC1)") (class "Default")
      (node (ref "J2") (pin "A5") (pinfunction "CC1_A5") (pintype "passive"))
      (node (ref "R3") (pin "2") (pinfunction "2_2") (pintype "passive"))
    )
    (net (code "43") (name "Net-(J2A-CC2)") (class "Default")
      (node (ref "J2") (pin "B5") (pinfunction "CC2_B5") (pintype "passive"))
      (node (ref "R7") (pin "2") (pinfunction "2_2") (pintype "passive"))
    )
    (net (code "44") (name "Net-(J3A-CC1)") (class "Default")
      (node (ref "J3") (pin "A5") (pinfunction "CC1_A5") (pintype "passive"))
      (node (ref "R4") (pin "2") (pinfunction "2_2") (pintype "passive"))
    )
    (net (code "45") (name "Net-(J3A-CC2)") (class "Default")
      (node (ref "J3") (pin "B5") (pinfunction "CC2_B5") (pintype "passive"))
      (node (ref "R8") (pin "2") (pinfunction "2_2") (pintype "passive"))
    )
    (net (code "46") (name "Net-(Q1-G)") (class "Default")
      (node (ref "Q1") (pin "1") (pinfunction "G_1") (pintype "passive"))
      (node (ref "R1") (pin "2") (pinfunction "2_2") (pintype "passive"))
    )
    (net (code "47") (name "Net-(Q2-G)") (class "Default")
      (node (ref "Q2") (pin "1") (pinfunction "G_1") (pintype "passive"))
      (node (ref "R5") (pin "2") (pinfunction "2_2") (pintype "passive"))
    )
    (net (code "48") (name "Net-(Q3-B)") (class "Default")
      (node (ref "Q3") (pin "1") (pinfunction "B_1") (pintype "passive"))
      (node (ref "R14") (pin "1") (pinfunction "1_1") (pintype "passive"))
    )
    (net (code "49") (name "Net-(Q3-C)") (class "Default")
      (node (ref "Q3") (pin "3") (pinfunction "C_3") (pintype "passive"))
      (node (ref "R16") (pin "2") (pinfunction "2_2") (pintype "passive"))
      (node (ref "R17") (pin "2") (pinfunction "2_2") (pintype "passive"))
    )
    (net (code "50") (name "Net-(Q4-G)") (class "Default")
      (node (ref "Q4") (pin "1") (pinfunction "G_1") (pintype "passive"))
      (node (ref "R15") (pin "1") (pinfunction "1_1") (pintype "passive"))
    )
    (net (code "51") (name "Net-(Q5-B)") (class "Default")
      (node (ref "C17") (pin "2") (pinfunction "2_2") (pintype "passive"))
      (node (ref "Q5") (pin "1") (pinfunction "B_1") (pintype "passive"))
      (node (ref "R16") (pin "1") (pinfunction "1_1") (pintype "passive"))
    )
    (net (code "52") (name "Net-(Q5-C)") (class "Default")
      (node (ref "Q5") (pin "3") (pinfunction "C_3") (pintype "passive"))
      (node (ref "R13") (pin "2") (pinfunction "2_2") (pintype "passive"))
      (node (ref "R15") (pin "2") (pinfunction "2_2") (pintype "passive"))
    )
    (net (code "53") (name "Net-(Q6-G)") (class "Default")
      (node (ref "Q6") (pin "1") (pinfunction "G_1") (pintype "passive"))
      (node (ref "R27") (pin "2") (pinfunction "2_2") (pintype "passive"))
    )
    (net (code "54") (name "Net-(U2-OUT)") (class "Default")
      (node (ref "R18") (pin "2") (pinfunction "2_2") (pintype "passive"))
      (node (ref "R19") (pin "2") (pinfunction "2_2") (pintype "passive"))
      (node (ref "R20") (pin "2") (pinfunction "2_2") (pintype "passive"))
      (node (ref "R21") (pin "2") (pinfunction "2_2") (pintype "passive"))
      (node (ref "U2") (pin "3") (pinfunction "OUT_3") (pintype "passive"))
    )
    (net (code "55") (name "Net-(U3-PA30)") (class "Default")
      (node (ref "JP3") (pin "1") (pinfunction "1_1") (pintype "passive"))
      (node (ref "U3") (pin "7") (pinfunction "PA30_7") (pintype "passive"))
    )
    (net (code "56") (name "Net-(U3-PA31)") (class "Default")
      (node (ref "JP1") (pin "1") (pinfunction "1_1") (pintype "passive"))
      (node (ref "U3") (pin "8") (pinfunction "PA31_8") (pintype "passive"))
    )
    (net (code "57") (name "Net-(U3-~{RST})") (class "Default")
      (node (ref "C8") (pin "2") (pinfunction "2_2") (pintype "passive"))
      (node (ref "JP5") (pin "1") (pinfunction "1_1") (pintype "passive"))
      (node (ref "R9") (pin "2") (pinfunction "2_2") (pintype "passive"))
      (node (ref "U3") (pin "6") (pinfunction "~{RST}_6") (pintype "passive"))
    )
    (net (code "58") (name "Net-(U4-PA30)") (class "Default")
      (node (ref "JP4") (pin "1") (pinfunction "1_1") (pintype "passive"))
      (node (ref "U4") (pin "7") (pinfunction "PA30_7") (pintype "passive"))
    )
    (net (code "59") (name "Net-(U4-PA31)") (class "Default")
      (node (ref "JP2") (pin "1") (pinfunction "1_1") (pintype "passive"))
      (node (ref "U4") (pin "8") (pinfunction "PA31_8") (pintype "passive"))
    )
    (net (code "60") (name "Net-(U4-~{RST})") (class "Default")
      (node (ref "C10") (pin "2") (pinfunction "2_2") (pintype "passive"))
      (node (ref "JP6") (pin "1") (pinfunction "1_1") (pintype "passive"))
      (node (ref "R10") (pin "2") (pinfunction "2_2") (pintype "passive"))
      (node (ref "U4") (pin "6") (pinfunction "~{RST}_6") (pintype "passive"))
    )
    (net (code "61") (name "Net-(U6-PA14)") (class "Default")
      (node (ref "R23") (pin "1") (pinfunction "1_1") (pintype "passive"))
      (node (ref "U6") (pin "4") (pinfunction "PA14_4") (pintype "passive"))
    )
    (net (code "62") (name "Net-(U6-PA15)") (class "Default")
      (node (ref "R24") (pin "1") (pinfunction "1_1") (pintype "passive"))
      (node (ref "U6") (pin "5") (pinfunction "PA15_5") (pintype "passive"))
    )
    (net (code "63") (name "Net-(U6-PA30)") (class "Default")
      (node (ref "JP10") (pin "1") (pinfunction "1_1") (pintype "passive"))
      (node (ref "R25") (pin "1") (pinfunction "1_1") (pintype "passive"))
      (node (ref "U6") (pin "7") (pinfunction "PA30_7") (pintype "passive"))
    )
    (net (code "64") (name "Net-(U6-PA31)") (class "Default")
      (node (ref "JP8") (pin "1") (pinfunction "1_1") (pintype "passive"))
      (node (ref "R26") (pin "2") (pinfunction "2_2") (pintype "passive"))
      (node (ref "U6") (pin "8") (pinfunction "PA31_8") (pintype "passive"))
    )
    (net (code "65") (name "Net-(U6-~{RST})") (class "Default")
      (node (ref "C14") (pin "2") (pinfunction "2_2") (pintype "passive"))
      (node (ref "JP12") (pin "1") (pinfunction "1_1") (pintype "passive"))
      (node (ref "R11") (pin "2") (pinfunction "2_2") (pintype "passive"))
      (node (ref "U6") (pin "6") (pinfunction "~{RST}_6") (pintype "passive"))
    )
    (net (code "66") (name "Net-(U7-PA30)") (class "Default")
      (node (ref "JP11") (pin "1") (pinfunction "1_1") (pintype "passive"))
      (node (ref "R22") (pin "1") (pinfunction "1_1") (pintype "passive"))
      (node (ref "U7") (pin "7") (pinfunction "PA30_7") (pintype "passive"))
    )
    (net (code "67") (name "Net-(U7-~{RST})") (class "Default")
      (node (ref "C16") (pin "2") (pinfunction "2_2") (pintype "passive"))
      (node (ref "JP13") (pin "1") (pinfunction "1_1") (pintype "passive"))
      (node (ref "R12") (pin "2") (pinfunction "2_2") (pintype "passive"))
      (node (ref "U7") (pin "6") (pinfunction "~{RST}_6") (pintype "passive"))
    )
    (net (code "68") (name "O1_5V") (class "Default")
      (node (ref "D3") (pin "5") (pinfunction "VBUS_5") (pintype "power_in"))
      (node (ref "J1") (pin "A4-B9") (pinfunction "VBUS_A4-B9") (pintype "power_in"))
      (node (ref "J1") (pin "B4-A9") (pinfunction "VBUS_B4-A9") (pintype "power_in"))
      (node (ref "Q1") (pin "2") (pinfunction "D_2") (pintype "passive"))
    )
    (net (code "69") (name "O2_5V") (class "Default")
      (node (ref "D4") (pin "5") (pinfunction "VBUS_5") (pintype "power_in"))
      (node (ref "J2") (pin "A4-B9") (pinfunction "VBUS_A4-B9") (pintype "power_in"))
      (node (ref "J2") (pin "B4-A9") (pinfunction "VBUS_B4-A9") (pintype "power_in"))
      (node (ref "Q2") (pin "2") (pinfunction "D_2") (pintype "passive"))
    )
    (net (code "70") (name "O3_5V") (class "Default")
      (node (ref "D5") (pin "5") (pinfunction "VBUS_5") (pintype "power_in"))
      (node (ref "J3") (pin "A4-B9") (pinfunction "VBUS_A4-B9") (pintype "power_in"))
      (node (ref "J3") (pin "B4-A9") (pinfunction "VBUS_B4-A9") (pintype "power_in"))
      (node (ref "Q6") (pin "2") (pinfunction "D_2") (pintype "passive"))
    )
    (net (code "71") (name "Vdd") (class "Default")
      (node (ref "C13") (pin "1") (pinfunction "1_1") (pintype "passive"))
      (node (ref "C15") (pin "1") (pinfunction "1_1") (pintype "passive"))
      (node (ref "C2") (pin "1") (pinfunction "1_1") (pintype "passive"))
      (node (ref "C4") (pin "2") (pinfunction "2_2") (pintype "passive"))
      (node (ref "C5") (pin "2") (pinfunction "2_2") (pintype "passive"))
      (node (ref "C7") (pin "1") (pinfunction "1_1") (pintype "passive"))
      (node (ref "C9") (pin "1") (pinfunction "1_1") (pintype "passive"))
      (node (ref "Q3") (pin "2") (pinfunction "E_2") (pintype "passive"))
      (node (ref "R10") (pin "1") (pinfunction "1_1") (pintype "passive"))
      (node (ref "R11") (pin "1") (pinfunction "1_1") (pintype "passive"))
      (node (ref "R12") (pin "1") (pinfunction "1_1") (pintype "passive"))
      (node (ref "R9") (pin "1") (pinfunction "1_1") (pintype "passive"))
      (node (ref "U1") (pin "2") (pinfunction "OUTPUT_2") (pintype "output"))
      (node (ref "U2") (pin "1") (pinfunction "EN_1") (pintype "passive"))
      (node (ref "U2") (pin "4") (pinfunction "VCC_4") (pintype "passive"))
      (node (ref "U3") (pin "12") (pinfunction "VDD_12") (pintype "passive"))
      (node (ref "U4") (pin "12") (pinfunction "VDD_12") (pintype "passive"))
      (node (ref "U6") (pin "12") (pinfunction "VDD_12") (pintype "passive"))
      (node (ref "U7") (pin "12") (pinfunction "VDD_12") (pintype "passive"))
    )
    (net (code "72") (name "unconnected-(J1A-SBU1-PadA8)") (class "Default")
      (node (ref "J1") (pin "A8") (pinfunction "SBU1_A8") (pintype "passive"))
    )
    (net (code "73") (name "unconnected-(J1A-SBU2-PadB8)") (class "Default")
      (node (ref "J1") (pin "B8") (pinfunction "SBU2_B8") (pintype "passive"))
    )
    (net (code "74") (name "unconnected-(J2A-SBU1-PadA8)") (class "Default")
      (node (ref "J2") (pin "A8") (pinfunction "SBU1_A8") (pintype "passive"))
    )
    (net (code "75") (name "unconnected-(J2A-SBU2-PadB8)") (class "Default")
      (node (ref "J2") (pin "B8") (pinfunction "SBU2_B8") (pintype "passive"))
    )
    (net (code "76") (name "unconnected-(J3A-SBU1-PadA8)") (class "Default")
      (node (ref "J3") (pin "A8") (pinfunction "SBU1_A8") (pintype "passive"))
    )
    (net (code "77") (name "unconnected-(J3A-SBU2-PadB8)") (class "Default")
      (node (ref "J3") (pin "B8") (pinfunction "SBU2_B8") (pintype "passive"))
    )
    (net (code "78") (name "unconnected-(U3-PA09-Pad3)") (class "Default")
      (node (ref "U3") (pin "3") (pinfunction "PA09_3") (pintype "passive"))
    )
    (net (code "79") (name "unconnected-(U4-PA09-Pad3)") (class "Default")
      (node (ref "U4") (pin "3") (pinfunction "PA09_3") (pintype "passive"))
    )
    (net (code "80") (name "unconnected-(U6-PA02-Pad13)") (class "Default")
      (node (ref "U6") (pin "13") (pinfunction "PA02_13") (pintype "passive"))
    )
  )
)
